# ltc3886_breakout_circuit.net
KiCad netlist of a schematic drawn in EAGLE
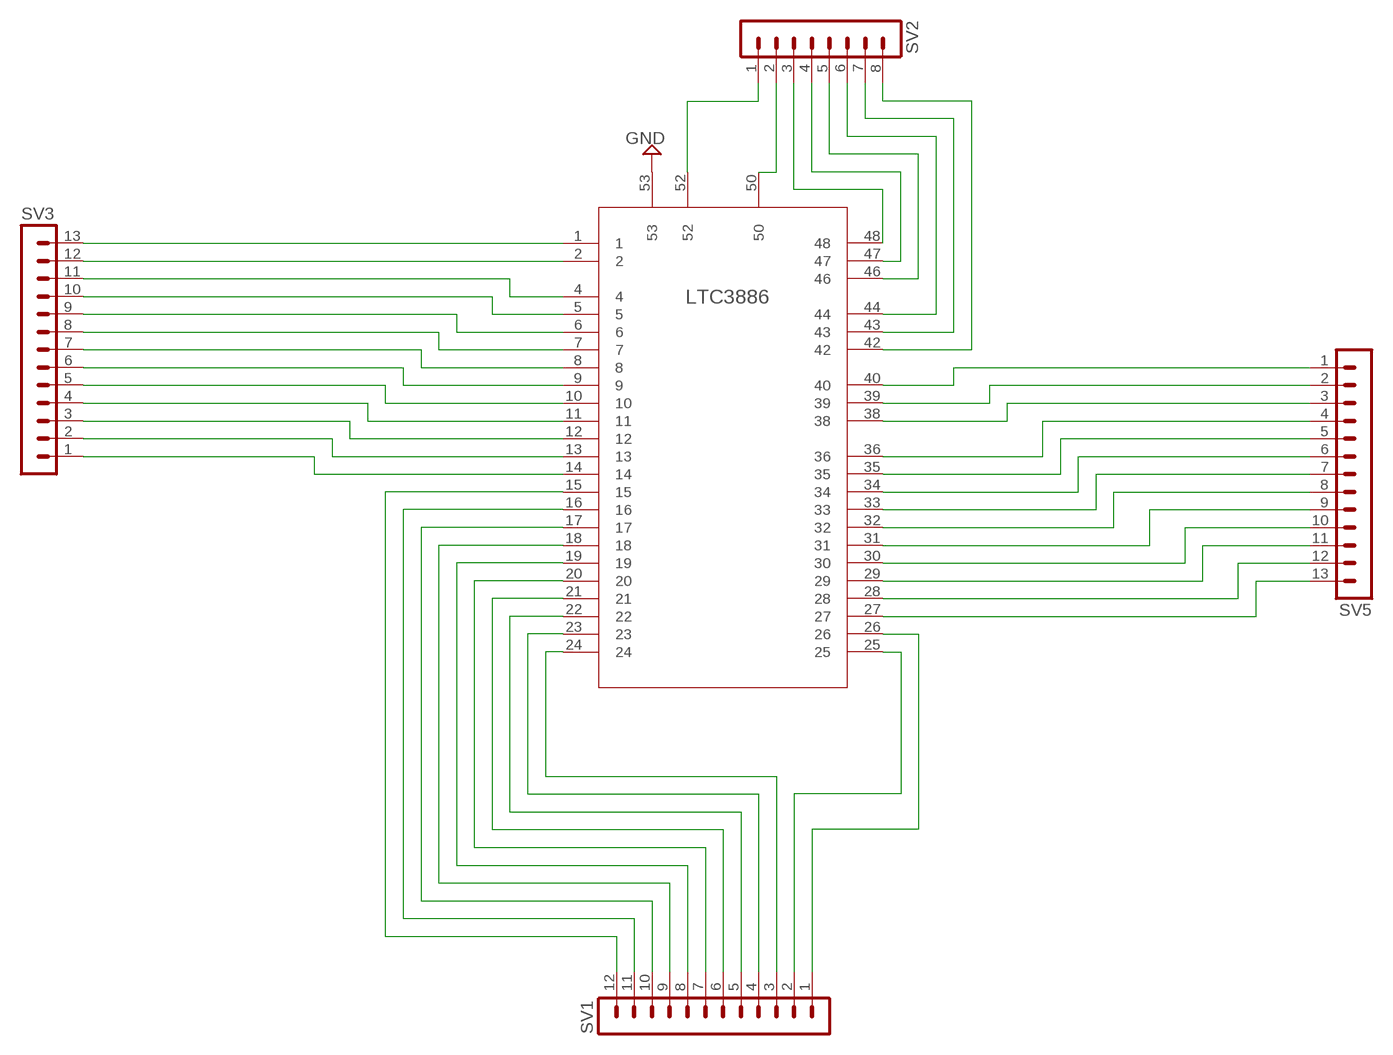
[diagram p0: schematic, sheet 1]

(export (version "E")
  (design (tool "Eeschema 10.0.6"))
  (components
    (comp (ref "SV1")
      (value "MA12-1")
      (footprint "eagle-import:MA12-1")
      (libsource (lib "eagle-import") (part "MA12-1"))
    )
    (comp (ref "SV2")
      (value "MA08-1")
      (footprint "eagle-import:MA08-1")
      (libsource (lib "eagle-import") (part "MA08-1"))
    )
    (comp (ref "SV3")
      (value "MA13-1")
      (footprint "eagle-import:MA13-1")
      (libsource (lib "eagle-import") (part "MA13-1"))
    )
    (comp (ref "SV5")
      (value "MA13-1")
      (footprint "eagle-import:MA13-1")
      (libsource (lib "eagle-import") (part "MA13-1"))
    )
    (comp (ref "U$1")
      (value "LTC3886")
      (footprint "eagle-import:QFN-52_UKG_2")
      (libsource (lib "eagle-import") (part "LTC3886"))
    )
  )
  (nets
    (net (code "1") (name "GND") (class "Default")
      (node (ref "U$1") (pin "53") (pinfunction "53_53") (pintype "bidirectional"))
    )
    (net (code "2") (name "Net-(SV1-Pad1)") (class "Default")
      (node (ref "SV1") (pin "1") (pinfunction "1_1") (pintype "passive"))
      (node (ref "U$1") (pin "26") (pinfunction "26_26") (pintype "passive"))
    )
    (net (code "3") (name "Net-(SV1-Pad2)") (class "Default")
      (node (ref "SV1") (pin "2") (pinfunction "2_2") (pintype "passive"))
      (node (ref "U$1") (pin "25") (pinfunction "25_25") (pintype "passive"))
    )
    (net (code "4") (name "Net-(SV1-Pad3)") (class "Default")
      (node (ref "SV1") (pin "3") (pinfunction "3_3") (pintype "passive"))
      (node (ref "U$1") (pin "24") (pinfunction "24_24") (pintype "passive"))
    )
    (net (code "5") (name "Net-(SV1-Pad4)") (class "Default")
      (node (ref "SV1") (pin "4") (pinfunction "4_4") (pintype "passive"))
      (node (ref "U$1") (pin "23") (pinfunction "23_23") (pintype "passive"))
    )
    (net (code "6") (name "Net-(SV1-Pad5)") (class "Default")
      (node (ref "SV1") (pin "5") (pinfunction "5_5") (pintype "passive"))
      (node (ref "U$1") (pin "22") (pinfunction "22_22") (pintype "passive"))
    )
    (net (code "7") (name "Net-(SV1-Pad6)") (class "Default")
      (node (ref "SV1") (pin "6") (pinfunction "6_6") (pintype "passive"))
      (node (ref "U$1") (pin "21") (pinfunction "21_21") (pintype "passive"))
    )
    (net (code "8") (name "Net-(SV1-Pad7)") (class "Default")
      (node (ref "SV1") (pin "7") (pinfunction "7_7") (pintype "passive"))
      (node (ref "U$1") (pin "20") (pinfunction "20_20") (pintype "passive"))
    )
    (net (code "9") (name "Net-(SV1-Pad8)") (class "Default")
      (node (ref "SV1") (pin "8") (pinfunction "8_8") (pintype "passive"))
      (node (ref "U$1") (pin "19") (pinfunction "19_19") (pintype "passive"))
    )
    (net (code "10") (name "Net-(SV1-Pad9)") (class "Default")
      (node (ref "SV1") (pin "9") (pinfunction "9_9") (pintype "passive"))
      (node (ref "U$1") (pin "18") (pinfunction "18_18") (pintype "passive"))
    )
    (net (code "11") (name "Net-(SV1-Pad10)") (class "Default")
      (node (ref "SV1") (pin "10") (pinfunction "10_10") (pintype "passive"))
      (node (ref "U$1") (pin "17") (pinfunction "17_17") (pintype "passive"))
    )
    (net (code "12") (name "Net-(SV1-Pad11)") (class "Default")
      (node (ref "SV1") (pin "11") (pinfunction "11_11") (pintype "passive"))
      (node (ref "U$1") (pin "16") (pinfunction "16_16") (pintype "passive"))
    )
    (net (code "13") (name "Net-(SV1-Pad12)") (class "Default")
      (node (ref "SV1") (pin "12") (pinfunction "12_12") (pintype "passive"))
      (node (ref "U$1") (pin "15") (pinfunction "15_15") (pintype "passive"))
    )
    (net (code "14") (name "Net-(SV2-Pad1)") (class "Default")
      (node (ref "SV2") (pin "1") (pinfunction "1_1") (pintype "passive"))
      (node (ref "U$1") (pin "52") (pinfunction "52_52") (pintype "bidirectional"))
    )
    (net (code "15") (name "Net-(SV2-Pad2)") (class "Default")
      (node (ref "SV2") (pin "2") (pinfunction "2_2") (pintype "passive"))
      (node (ref "U$1") (pin "50") (pinfunction "50_50") (pintype "bidirectional"))
    )
    (net (code "16") (name "Net-(SV2-Pad3)") (class "Default")
      (node (ref "SV2") (pin "3") (pinfunction "3_3") (pintype "passive"))
      (node (ref "U$1") (pin "48") (pinfunction "48_48") (pintype "passive"))
    )
    (net (code "17") (name "Net-(SV2-Pad4)") (class "Default")
      (node (ref "SV2") (pin "4") (pinfunction "4_4") (pintype "passive"))
      (node (ref "U$1") (pin "47") (pinfunction "47_47") (pintype "passive"))
    )
    (net (code "18") (name "Net-(SV2-Pad5)") (class "Default")
      (node (ref "SV2") (pin "5") (pinfunction "5_5") (pintype "passive"))
      (node (ref "U$1") (pin "46") (pinfunction "46_46") (pintype "passive"))
    )
    (net (code "19") (name "Net-(SV2-Pad6)") (class "Default")
      (node (ref "SV2") (pin "6") (pinfunction "6_6") (pintype "passive"))
      (node (ref "U$1") (pin "44") (pinfunction "44_44") (pintype "passive"))
    )
    (net (code "20") (name "Net-(SV2-Pad7)") (class "Default")
      (node (ref "SV2") (pin "7") (pinfunction "7_7") (pintype "passive"))
      (node (ref "U$1") (pin "43") (pinfunction "43_43") (pintype "passive"))
    )
    (net (code "21") (name "Net-(SV2-Pad8)") (class "Default")
      (node (ref "SV2") (pin "8") (pinfunction "8_8") (pintype "passive"))
      (node (ref "U$1") (pin "42") (pinfunction "42_42") (pintype "passive"))
    )
    (net (code "22") (name "Net-(SV3-Pad1)") (class "Default")
      (node (ref "SV3") (pin "1") (pinfunction "1_1") (pintype "passive"))
      (node (ref "U$1") (pin "14") (pinfunction "14_14") (pintype "passive"))
    )
    (net (code "23") (name "Net-(SV3-Pad2)") (class "Default")
      (node (ref "SV3") (pin "2") (pinfunction "2_2") (pintype "passive"))
      (node (ref "U$1") (pin "13") (pinfunction "13_13") (pintype "passive"))
    )
    (net (code "24") (name "Net-(SV3-Pad3)") (class "Default")
      (node (ref "SV3") (pin "3") (pinfunction "3_3") (pintype "passive"))
      (node (ref "U$1") (pin "12") (pinfunction "12_12") (pintype "passive"))
    )
    (net (code "25") (name "Net-(SV3-Pad4)") (class "Default")
      (node (ref "SV3") (pin "4") (pinfunction "4_4") (pintype "passive"))
      (node (ref "U$1") (pin "11") (pinfunction "11_11") (pintype "passive"))
    )
    (net (code "26") (name "Net-(SV3-Pad5)") (class "Default")
      (node (ref "SV3") (pin "5") (pinfunction "5_5") (pintype "passive"))
      (node (ref "U$1") (pin "10") (pinfunction "10_10") (pintype "passive"))
    )
    (net (code "27") (name "Net-(SV3-Pad6)") (class "Default")
      (node (ref "SV3") (pin "6") (pinfunction "6_6") (pintype "passive"))
      (node (ref "U$1") (pin "9") (pinfunction "9_9") (pintype "passive"))
    )
    (net (code "28") (name "Net-(SV3-Pad7)") (class "Default")
      (node (ref "SV3") (pin "7") (pinfunction "7_7") (pintype "passive"))
      (node (ref "U$1") (pin "8") (pinfunction "8_8") (pintype "passive"))
    )
    (net (code "29") (name "Net-(SV3-Pad8)") (class "Default")
      (node (ref "SV3") (pin "8") (pinfunction "8_8") (pintype "passive"))
      (node (ref "U$1") (pin "7") (pinfunction "7_7") (pintype "passive"))
    )
    (net (code "30") (name "Net-(SV3-Pad9)") (class "Default")
      (node (ref "SV3") (pin "9") (pinfunction "9_9") (pintype "passive"))
      (node (ref "U$1") (pin "6") (pinfunction "6_6") (pintype "passive"))
    )
    (net (code "31") (name "Net-(SV3-Pad10)") (class "Default")
      (node (ref "SV3") (pin "10") (pinfunction "10_10") (pintype "passive"))
      (node (ref "U$1") (pin "5") (pinfunction "5_5") (pintype "passive"))
    )
    (net (code "32") (name "Net-(SV3-Pad11)") (class "Default")
      (node (ref "SV3") (pin "11") (pinfunction "11_11") (pintype "passive"))
      (node (ref "U$1") (pin "4") (pinfunction "4_4") (pintype "passive"))
    )
    (net (code "33") (name "Net-(SV3-Pad12)") (class "Default")
      (node (ref "SV3") (pin "12") (pinfunction "12_12") (pintype "passive"))
      (node (ref "U$1") (pin "2") (pinfunction "2_2") (pintype "passive"))
    )
    (net (code "34") (name "Net-(SV3-Pad13)") (class "Default")
      (node (ref "SV3") (pin "13") (pinfunction "13_13") (pintype "passive"))
      (node (ref "U$1") (pin "1") (pinfunction "1_1") (pintype "passive"))
    )
    (net (code "35") (name "Net-(SV5-Pad1)") (class "Default")
      (node (ref "SV5") (pin "1") (pinfunction "1_1") (pintype "passive"))
      (node (ref "U$1") (pin "40") (pinfunction "40_40") (pintype "passive"))
    )
    (net (code "36") (name "Net-(SV5-Pad2)") (class "Default")
      (node (ref "SV5") (pin "2") (pinfunction "2_2") (pintype "passive"))
      (node (ref "U$1") (pin "39") (pinfunction "39_39") (pintype "passive"))
    )
    (net (code "37") (name "Net-(SV5-Pad3)") (class "Default")
      (node (ref "SV5") (pin "3") (pinfunction "3_3") (pintype "passive"))
      (node (ref "U$1") (pin "38") (pinfunction "38_38") (pintype "passive"))
    )
    (net (code "38") (name "Net-(SV5-Pad4)") (class "Default")
      (node (ref "SV5") (pin "4") (pinfunction "4_4") (pintype "passive"))
      (node (ref "U$1") (pin "36") (pinfunction "36_36") (pintype "passive"))
    )
    (net (code "39") (name "Net-(SV5-Pad5)") (class "Default")
      (node (ref "SV5") (pin "5") (pinfunction "5_5") (pintype "passive"))
      (node (ref "U$1") (pin "35") (pinfunction "35_35") (pintype "passive"))
    )
    (net (code "40") (name "Net-(SV5-Pad6)") (class "Default")
      (node (ref "SV5") (pin "6") (pinfunction "6_6") (pintype "passive"))
      (node (ref "U$1") (pin "34") (pinfunction "34_34") (pintype "passive"))
    )
    (net (code "41") (name "Net-(SV5-Pad7)") (class "Default")
      (node (ref "SV5") (pin "7") (pinfunction "7_7") (pintype "passive"))
      (node (ref "U$1") (pin "33") (pinfunction "33_33") (pintype "passive"))
    )
    (net (code "42") (name "Net-(SV5-Pad8)") (class "Default")
      (node (ref "SV5") (pin "8") (pinfunction "8_8") (pintype "passive"))
      (node (ref "U$1") (pin "32") (pinfunction "32_32") (pintype "passive"))
    )
    (net (code "43") (name "Net-(SV5-Pad9)") (class "Default")
      (node (ref "SV5") (pin "9") (pinfunction "9_9") (pintype "passive"))
      (node (ref "U$1") (pin "31") (pinfunction "31_31") (pintype "passive"))
    )
    (net (code "44") (name "Net-(SV5-Pad10)") (class "Default")
      (node (ref "SV5") (pin "10") (pinfunction "10_10") (pintype "passive"))
      (node (ref "U$1") (pin "30") (pinfunction "30_30") (pintype "passive"))
    )
    (net (code "45") (name "Net-(SV5-Pad11)") (class "Default")
      (node (ref "SV5") (pin "11") (pinfunction "11_11") (pintype "passive"))
      (node (ref "U$1") (pin "29") (pinfunction "29_29") (pintype "passive"))
    )
    (net (code "46") (name "Net-(SV5-Pad12)") (class "Default")
      (node (ref "SV5") (pin "12") (pinfunction "12_12") (pintype "passive"))
      (node (ref "U$1") (pin "28") (pinfunction "28_28") (pintype "passive"))
    )
    (net (code "47") (name "Net-(SV5-Pad13)") (class "Default")
      (node (ref "SV5") (pin "13") (pinfunction "13_13") (pintype "passive"))
      (node (ref "U$1") (pin "27") (pinfunction "27_27") (pintype "passive"))
    )
  )
)
